# PWR-1-cell_Li-ion_charger.net
KiCad netlist of a schematic drawn in Altium Designer
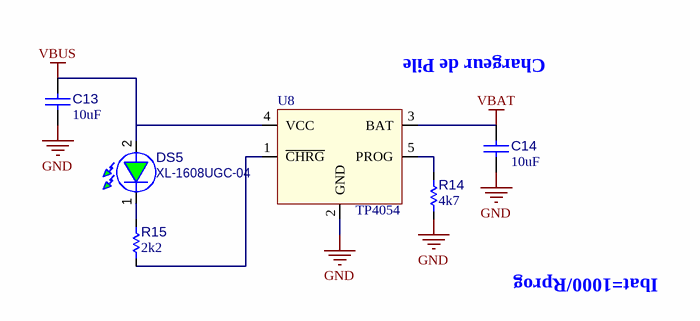
[diagram p0: PWR-1-cell Li-ion charger.SchDoc]

(export (version "E")
  (design (tool "Eeschema 10.0.6"))
  (components
    (comp (ref "C13")
      (value "10uF")
      (footprint "C_2012[0805]")
      (description "Capacitor type 1")
      (fields (field (name "TOLERANCE") "10%") (field (name "Comment") "Cap 10uF 0805"))
      (libsource (lib "TEP_243-Altium_DBLib") (part "capacitor"))
    )
    (comp (ref "C14")
      (value "10uF")
      (footprint "C_2012[0805]")
      (description "Capacitor type 1")
      (fields (field (name "TOLERANCE") "10%") (field (name "Comment") "Cap 10uF 0805"))
      (libsource (lib "TEP_243-Altium_DBLib") (part "capacitor"))
    )
    (comp (ref "DS5")
      (value "XL-1608UGC-04")
      (footprint "D_LED_0603")
      (description "LED Green Clear 40mcd 140deg")
      (libsource (lib "243-336_MP_Manette") (part "D_LED_GREEN_0603"))
    )
    (comp (ref "R14")
      (value "4k7")
      (footprint "R_1005[0402]")
      (description "Resistor type 1")
      (fields (field (name "TOLERANCE") "1%") (field (name "Comment") "Res 4k7 1% 0402"))
      (libsource (lib "TEP_243-Altium_DBLib") (part "resistor"))
    )
    (comp (ref "R15")
      (value "2k2")
      (footprint "R_1005[0402]")
      (description "Resistor type 1")
      (fields (field (name "TOLERANCE") "1%") (field (name "Comment") "Res 2k2 1% 0402"))
      (libsource (lib "TEP_243-Altium_DBLib") (part "resistor"))
    )
    (comp (ref "U8")
      (value "TP4054")
      (footprint "U_SOT23-5N(MO-178)")
      (description "Battery charger Li-ion Linear 1-cell")
      (libsource (lib "243-336_MP_Manette") (part "U_TP4054"))
    )
  )
  (nets
    (net (code "1") (name "GND") (class "Default")
      (node (ref "C13") (pin "1") (pinfunction "1_1") (pintype "passive"))
      (node (ref "C14") (pin "1") (pinfunction "1_1") (pintype "passive"))
      (node (ref "R14") (pin "1") (pinfunction "1_1") (pintype "passive"))
      (node (ref "U8") (pin "2") (pinfunction "GND_2") (pintype "power_in"))
    )
    (net (code "2") (name "Net-(DS5-K)") (class "Default")
      (node (ref "DS5") (pin "1") (pinfunction "K_1") (pintype "passive"))
      (node (ref "R15") (pin "2") (pinfunction "2_2") (pintype "passive"))
    )
    (net (code "3") (name "Net-(U8-PROG)") (class "Default")
      (node (ref "R14") (pin "2") (pinfunction "2_2") (pintype "passive"))
      (node (ref "U8") (pin "5") (pinfunction "PROG_5") (pintype "passive"))
    )
    (net (code "4") (name "Net-(U8-~{CHRG})") (class "Default")
      (node (ref "R15") (pin "1") (pinfunction "1_1") (pintype "passive"))
      (node (ref "U8") (pin "1") (pinfunction "~{CHRG}_1") (pintype "passive"))
    )
    (net (code "5") (name "VBAT") (class "Default")
      (node (ref "C14") (pin "2") (pinfunction "2_2") (pintype "passive"))
      (node (ref "U8") (pin "3") (pinfunction "BAT_3") (pintype "power_in"))
    )
    (net (code "6") (name "VBUS") (class "Default")
      (node (ref "C13") (pin "2") (pinfunction "2_2") (pintype "passive"))
      (node (ref "DS5") (pin "2") (pinfunction "A_2") (pintype "passive"))
      (node (ref "U8") (pin "4") (pinfunction "VCC_4") (pintype "power_in"))
    )
  )
)
